# Wiring-Board-Nano_lay.net
KiCad netlist of a schematic drawn in EAGLE
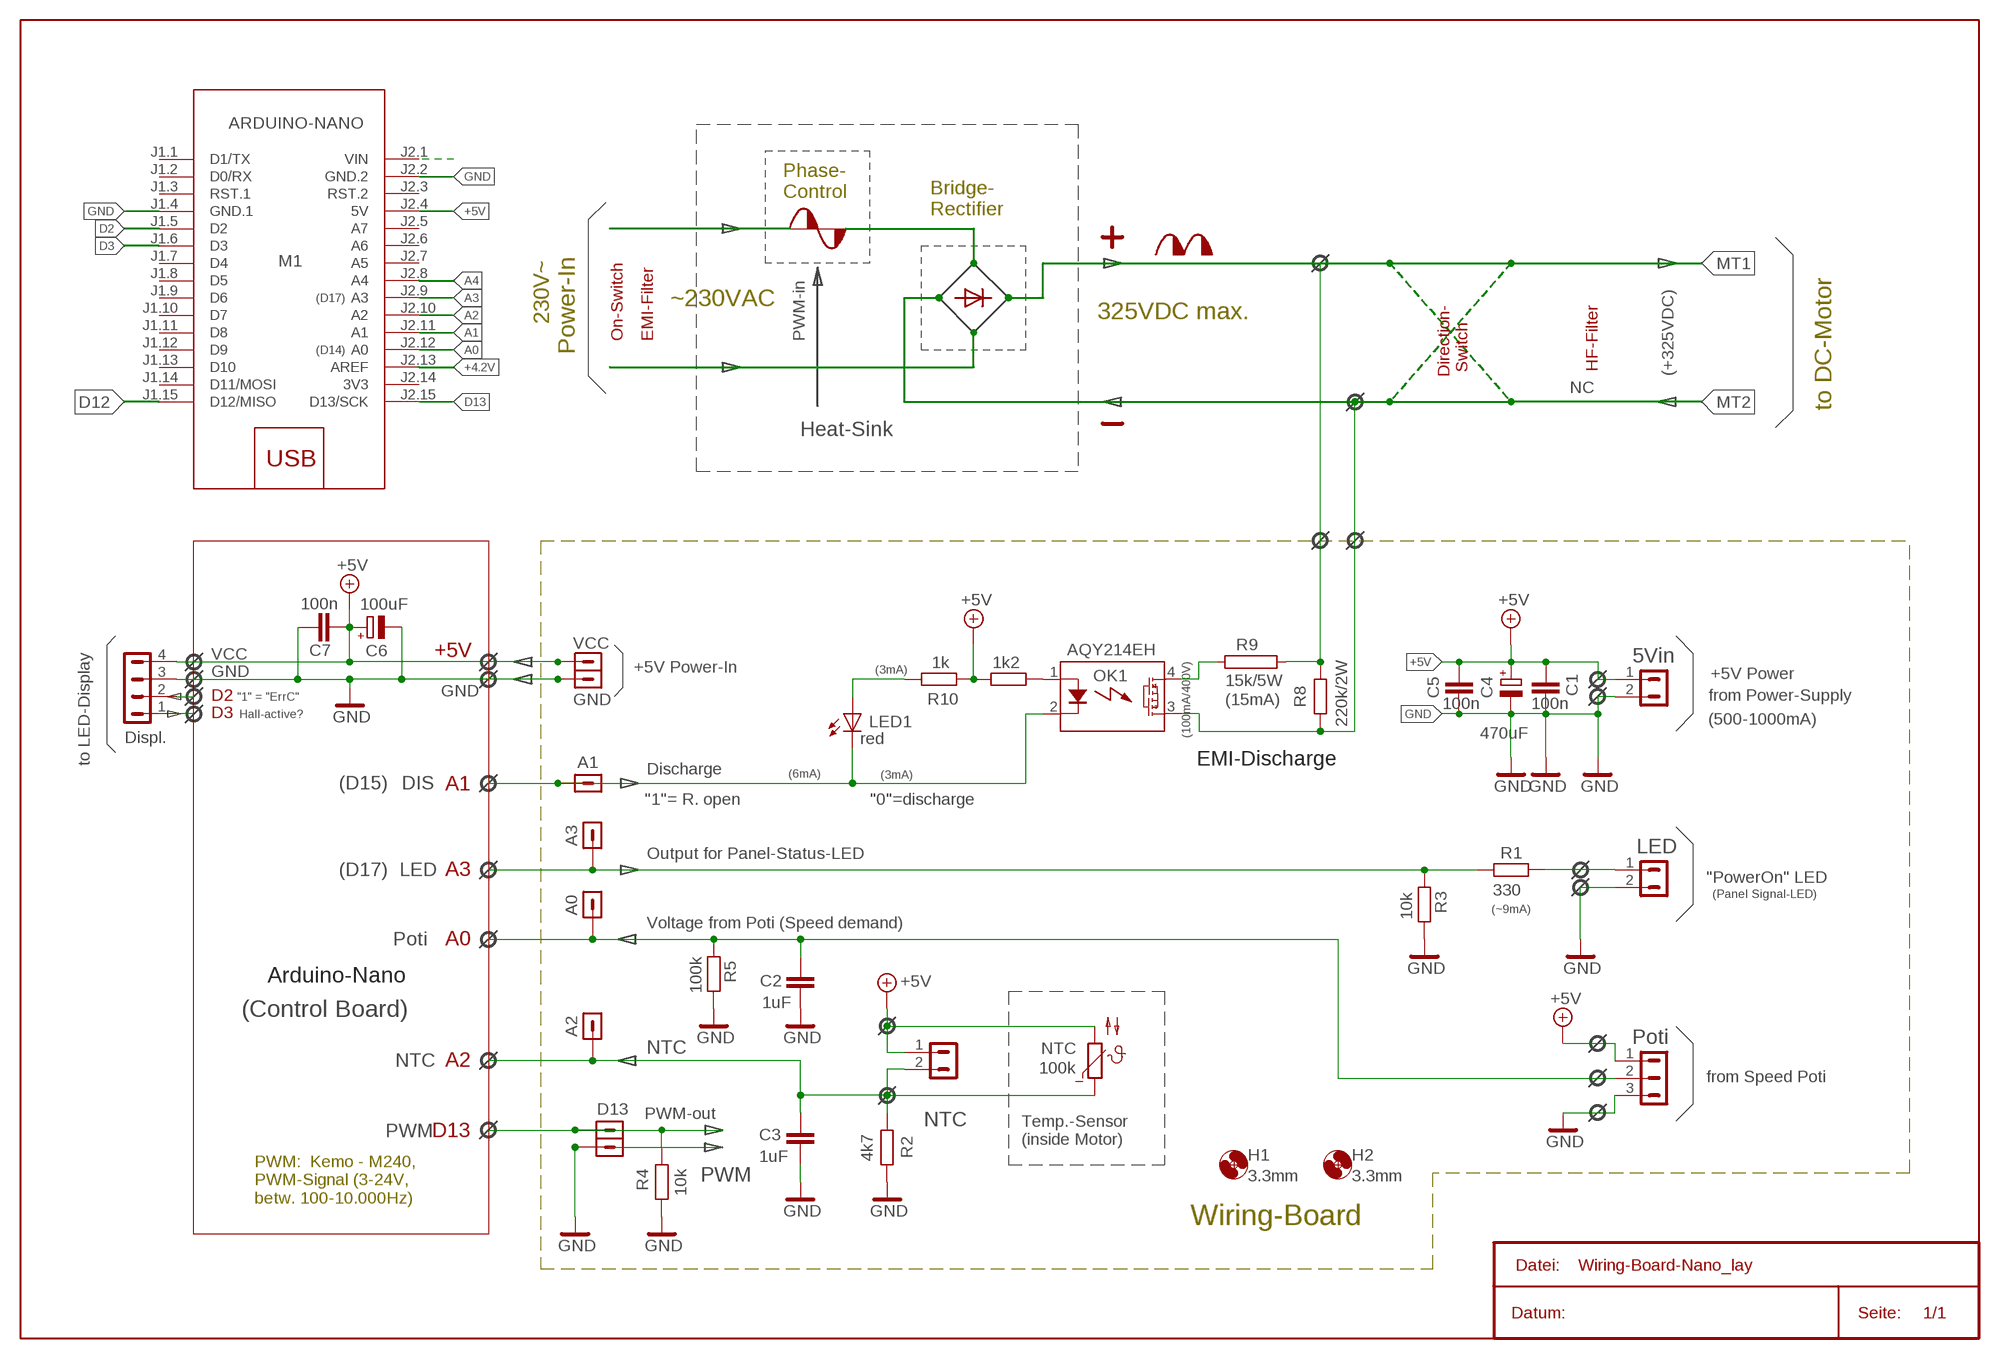
[diagram p0: schematic, sheet 1]

(export (version "E")
  (design (tool "Eeschema 10.0.6"))
  (components
    (comp (ref "C1")
      (value "100n")
      (footprint "eagle-import:C0805")
      (libsource (lib "eagle-import") (part "C-EUC0805"))
    )
    (comp (ref "C2")
      (value "1uF")
      (footprint "eagle-import:C0805")
      (libsource (lib "eagle-import") (part "C-EUC0805"))
    )
    (comp (ref "C3")
      (value "1uF")
      (footprint "eagle-import:C0805")
      (libsource (lib "eagle-import") (part "C-EUC0805"))
    )
    (comp (ref "C4")
      (value "470uF")
      (footprint "eagle-import:E3,5-8")
      (libsource (lib "eagle-import") (part "CPOL-EUE3.5-8"))
    )
    (comp (ref "C5")
      (value "100n")
      (footprint "eagle-import:C0805")
      (libsource (lib "eagle-import") (part "C-EUC0805"))
    )
    (comp (ref "C6")
      (value "100uF")
      (footprint "eagle-import:E2,5-7")
      (libsource (lib "eagle-import") (part "CPOL-EUE2.5-7"))
    )
    (comp (ref "C7")
      (value "100n")
      (footprint "eagle-import:C0805")
      (libsource (lib "eagle-import") (part "C-EUC0805"))
    )
    (comp (ref "H1")
      (value "3.3mm")
      (footprint "eagle-import:3,3")
      (libsource (lib "eagle-import") (part "MOUNT-HOLE3.3"))
    )
    (comp (ref "H2")
      (value "3.3mm")
      (footprint "eagle-import:3,3")
      (libsource (lib "eagle-import") (part "MOUNT-HOLE3.3"))
    )
    (comp (ref "LED1")
      (value "red")
      (footprint "eagle-import:CHIPLED_0805")
      (libsource (lib "eagle-import") (part "LEDCHIPLED_0805"))
    )
    (comp (ref "M1")
      (value "ARDUINO-NANO")
      (footprint "eagle-import:ARDUINO-NANO-3.0")
      (libsource (lib "eagle-import") (part "ARDUINO-NANO-3.0"))
    )
    (comp (ref "OK1")
      (value "AQY214EH")
      (footprint "eagle-import:GULLWING")
      (libsource (lib "eagle-import") (part "AQY"))
    )
    (comp (ref "R1")
      (value "330")
      (footprint "eagle-import:R0805")
      (libsource (lib "eagle-import") (part "R-EU_R0805"))
    )
    (comp (ref "R2")
      (value "4k7")
      (footprint "eagle-import:R0805")
      (libsource (lib "eagle-import") (part "R-EU_R0805"))
    )
    (comp (ref "R3")
      (value "10k")
      (footprint "eagle-import:R0805")
      (libsource (lib "eagle-import") (part "R-EU_R0805"))
    )
    (comp (ref "R4")
      (value "10k")
      (footprint "eagle-import:R0805")
      (libsource (lib "eagle-import") (part "R-EU_R0805"))
    )
    (comp (ref "R5")
      (value "100k")
      (footprint "eagle-import:R0805")
      (libsource (lib "eagle-import") (part "R-EU_R0805"))
    )
    (comp (ref "R8")
      (value "220k/2W")
      (footprint "eagle-import:0309_12")
      (libsource (lib "eagle-import") (part "R-EU_0309/12"))
    )
    (comp (ref "R9")
      (value "15k/5W")
      (footprint "eagle-import:KH206-8")
      (libsource (lib "eagle-import") (part "RKH206-8"))
    )
    (comp (ref "R10")
      (value "1k")
      (footprint "eagle-import:R0805")
      (libsource (lib "eagle-import") (part "R-EU_R0805"))
    )
    (comp (ref "R11")
      (value "1k2")
      (footprint "eagle-import:R0805")
      (libsource (lib "eagle-import") (part "R-EU_R0805"))
    )
    (comp (ref "SV1")
      (value "5Vin")
      (footprint "eagle-import:MA02-1")
      (libsource (lib "eagle-import") (part "MA02-10"))
    )
    (comp (ref "SV2")
      (value "LED")
      (footprint "eagle-import:MA02-1")
      (libsource (lib "eagle-import") (part "MA02-10"))
    )
    (comp (ref "SV3")
      (value "Poti")
      (footprint "eagle-import:MA03-1")
      (libsource (lib "eagle-import") (part "MA03-10"))
    )
    (comp (ref "SV4")
      (value "NTC")
      (footprint "eagle-import:MA02-1")
      (libsource (lib "eagle-import") (part "MA02-10"))
    )
    (comp (ref "SV6")
      (value "Displ.")
      (footprint "eagle-import:MA04-1")
      (libsource (lib "eagle-import") (part "MA04-10"))
    )
  )
  (nets
    (net (code "1") (name "+4.2V") (class "Default")
      (node (ref "M1") (pin "J2.13") (pinfunction "AREF_J2.13") (pintype "bidirectional"))
    )
    (net (code "2") (name "+5V") (class "Default")
      (node (ref "C1") (pin "1") (pinfunction "1_1") (pintype "passive"))
      (node (ref "C4") (pin "+") (pinfunction "+_+") (pintype "passive"))
      (node (ref "C5") (pin "1") (pinfunction "1_1") (pintype "passive"))
      (node (ref "C6") (pin "+") (pinfunction "+_+") (pintype "passive"))
      (node (ref "C7") (pin "1") (pinfunction "1_1") (pintype "passive"))
      (node (ref "M1") (pin "J2.4") (pinfunction "5V_J2.4") (pintype "power_in"))
      (node (ref "R10") (pin "2") (pinfunction "2_2") (pintype "passive"))
      (node (ref "R11") (pin "1") (pinfunction "1_1") (pintype "passive"))
      (node (ref "SV1") (pin "1") (pinfunction "1_1") (pintype "passive"))
      (node (ref "SV3") (pin "1") (pinfunction "1_1") (pintype "passive"))
      (node (ref "SV4") (pin "1") (pinfunction "1_1") (pintype "passive"))
      (node (ref "SV6") (pin "4") (pinfunction "4_4") (pintype "passive"))
    )
    (net (code "3") (name "/3V3") (class "Default")
      (node (ref "M1") (pin "J2.14") (pinfunction "3V3_J2.14") (pintype "power_in"))
    )
    (net (code "4") (name "A0") (class "Default")
      (node (ref "C2") (pin "1") (pinfunction "1_1") (pintype "passive"))
      (node (ref "M1") (pin "J2.12") (pinfunction "A0_J2.12") (pintype "bidirectional"))
      (node (ref "R5") (pin "1") (pinfunction "1_1") (pintype "passive"))
      (node (ref "SV3") (pin "2") (pinfunction "2_2") (pintype "passive"))
    )
    (net (code "5") (name "A1") (class "Default")
      (node (ref "LED1") (pin "C") (pinfunction "C_C") (pintype "passive"))
      (node (ref "M1") (pin "J2.11") (pinfunction "A1_J2.11") (pintype "bidirectional"))
      (node (ref "OK1") (pin "2") (pinfunction "K_2") (pintype "passive"))
    )
    (net (code "6") (name "A2") (class "Default")
      (node (ref "C3") (pin "1") (pinfunction "1_1") (pintype "passive"))
      (node (ref "M1") (pin "J2.10") (pinfunction "A2_J2.10") (pintype "bidirectional"))
      (node (ref "R2") (pin "2") (pinfunction "2_2") (pintype "passive"))
      (node (ref "SV4") (pin "2") (pinfunction "2_2") (pintype "passive"))
    )
    (net (code "7") (name "A3") (class "Default")
      (node (ref "M1") (pin "J2.9") (pinfunction "A3_J2.9") (pintype "bidirectional"))
      (node (ref "R1") (pin "1") (pinfunction "1_1") (pintype "passive"))
      (node (ref "R3") (pin "1") (pinfunction "1_1") (pintype "passive"))
    )
    (net (code "8") (name "A4") (class "Default")
      (node (ref "M1") (pin "J2.8") (pinfunction "A4_J2.8") (pintype "bidirectional"))
    )
    (net (code "9") (name "D2") (class "Default")
      (node (ref "M1") (pin "J1.5") (pinfunction "D2_J1.5") (pintype "bidirectional"))
      (node (ref "SV6") (pin "2") (pinfunction "2_2") (pintype "passive"))
    )
    (net (code "10") (name "D3") (class "Default")
      (node (ref "M1") (pin "J1.6") (pinfunction "D3_J1.6") (pintype "bidirectional"))
      (node (ref "SV6") (pin "1") (pinfunction "1_1") (pintype "passive"))
    )
    (net (code "11") (name "D12") (class "Default")
      (node (ref "M1") (pin "J1.15") (pinfunction "D12/MISO_J1.15") (pintype "bidirectional"))
    )
    (net (code "12") (name "D13") (class "Default")
      (node (ref "M1") (pin "J2.15") (pinfunction "D13/SCK_J2.15") (pintype "bidirectional"))
      (node (ref "R4") (pin "1") (pinfunction "1_1") (pintype "passive"))
    )
    (net (code "13") (name "GND") (class "Default")
      (node (ref "C1") (pin "2") (pinfunction "2_2") (pintype "passive"))
      (node (ref "C2") (pin "2") (pinfunction "2_2") (pintype "passive"))
      (node (ref "C3") (pin "2") (pinfunction "2_2") (pintype "passive"))
      (node (ref "C4") (pin "-") (pinfunction "-_-") (pintype "passive"))
      (node (ref "C5") (pin "2") (pinfunction "2_2") (pintype "passive"))
      (node (ref "C6") (pin "-") (pinfunction "-_-") (pintype "passive"))
      (node (ref "C7") (pin "2") (pinfunction "2_2") (pintype "passive"))
      (node (ref "M1") (pin "J1.4") (pinfunction "GND.1_J1.4") (pintype "power_in"))
      (node (ref "M1") (pin "J2.2") (pinfunction "GND.2_J2.2") (pintype "power_in"))
      (node (ref "R2") (pin "1") (pinfunction "1_1") (pintype "passive"))
      (node (ref "R3") (pin "2") (pinfunction "2_2") (pintype "passive"))
      (node (ref "R4") (pin "2") (pinfunction "2_2") (pintype "passive"))
      (node (ref "R5") (pin "2") (pinfunction "2_2") (pintype "passive"))
      (node (ref "SV1") (pin "2") (pinfunction "2_2") (pintype "passive"))
      (node (ref "SV2") (pin "2") (pinfunction "2_2") (pintype "passive"))
      (node (ref "SV3") (pin "3") (pinfunction "3_3") (pintype "passive"))
      (node (ref "SV6") (pin "3") (pinfunction "3_3") (pintype "passive"))
    )
    (net (code "14") (name "MT1") (class "Default")
      (node (ref "R8") (pin "2") (pinfunction "2_2") (pintype "passive"))
      (node (ref "R9") (pin "2") (pinfunction "2_2") (pintype "passive"))
    )
    (net (code "16") (name "Net-(LED1-PadA)") (class "Default")
      (node (ref "LED1") (pin "A") (pinfunction "A_A") (pintype "passive"))
      (node (ref "R10") (pin "1") (pinfunction "1_1") (pintype "passive"))
    )
    (net (code "17") (name "Net-(OK1-A)") (class "Default")
      (node (ref "OK1") (pin "1") (pinfunction "A_1") (pintype "passive"))
      (node (ref "R11") (pin "2") (pinfunction "2_2") (pintype "passive"))
    )
    (net (code "18") (name "Net-(OK1-DS1)") (class "Default")
      (node (ref "OK1") (pin "4") (pinfunction "DS1_4") (pintype "passive"))
      (node (ref "R9") (pin "1") (pinfunction "1_1") (pintype "passive"))
    )
    (net (code "19") (name "Net-(OK1-DS2)") (class "Default")
      (node (ref "OK1") (pin "3") (pinfunction "DS2_3") (pintype "passive"))
      (node (ref "R8") (pin "1") (pinfunction "1_1") (pintype "passive"))
    )
    (net (code "20") (name "Net-(R1-Pad2)") (class "Default")
      (node (ref "R1") (pin "2") (pinfunction "2_2") (pintype "passive"))
      (node (ref "SV2") (pin "1") (pinfunction "1_1") (pintype "passive"))
    )
    (net (code "21") (name "unconnected-(M1-A5-PadJ2.7)") (class "Default")
      (node (ref "M1") (pin "J2.7") (pinfunction "A5_J2.7") (pintype "bidirectional"))
    )
    (net (code "22") (name "unconnected-(M1-A6-PadJ2.6)") (class "Default")
      (node (ref "M1") (pin "J2.6") (pinfunction "A6_J2.6") (pintype "bidirectional"))
    )
    (net (code "23") (name "unconnected-(M1-A7-PadJ2.5)") (class "Default")
      (node (ref "M1") (pin "J2.5") (pinfunction "A7_J2.5") (pintype "bidirectional"))
    )
    (net (code "24") (name "unconnected-(M1-D0{slash}RX-PadJ1.2)") (class "Default")
      (node (ref "M1") (pin "J1.2") (pinfunction "D0/RX_J1.2") (pintype "bidirectional"))
    )
    (net (code "25") (name "unconnected-(M1-D1{slash}TX-PadJ1.1)") (class "Default")
      (node (ref "M1") (pin "J1.1") (pinfunction "D1/TX_J1.1") (pintype "bidirectional"))
    )
    (net (code "26") (name "unconnected-(M1-D4-PadJ1.7)") (class "Default")
      (node (ref "M1") (pin "J1.7") (pinfunction "D4_J1.7") (pintype "bidirectional"))
    )
    (net (code "27") (name "unconnected-(M1-D5-PadJ1.8)") (class "Default")
      (node (ref "M1") (pin "J1.8") (pinfunction "D5_J1.8") (pintype "bidirectional"))
    )
    (net (code "28") (name "unconnected-(M1-D6-PadJ1.9)") (class "Default")
      (node (ref "M1") (pin "J1.9") (pinfunction "D6_J1.9") (pintype "bidirectional"))
    )
    (net (code "29") (name "unconnected-(M1-D7-PadJ1.10)") (class "Default")
      (node (ref "M1") (pin "J1.10") (pinfunction "D7_J1.10") (pintype "bidirectional"))
    )
    (net (code "30") (name "unconnected-(M1-D8-PadJ1.11)") (class "Default")
      (node (ref "M1") (pin "J1.11") (pinfunction "D8_J1.11") (pintype "bidirectional"))
    )
    (net (code "31") (name "unconnected-(M1-D9-PadJ1.12)") (class "Default")
      (node (ref "M1") (pin "J1.12") (pinfunction "D9_J1.12") (pintype "bidirectional"))
    )
    (net (code "32") (name "unconnected-(M1-D10-PadJ1.13)") (class "Default")
      (node (ref "M1") (pin "J1.13") (pinfunction "D10_J1.13") (pintype "bidirectional"))
    )
    (net (code "33") (name "unconnected-(M1-D11{slash}MOSI-PadJ1.14)") (class "Default")
      (node (ref "M1") (pin "J1.14") (pinfunction "D11/MOSI_J1.14") (pintype "bidirectional"))
    )
    (net (code "34") (name "unconnected-(M1-RST.1-PadJ1.3)") (class "Default")
      (node (ref "M1") (pin "J1.3") (pinfunction "RST.1_J1.3") (pintype "bidirectional"))
    )
    (net (code "35") (name "unconnected-(M1-RST.2-PadJ2.3)") (class "Default")
      (node (ref "M1") (pin "J2.3") (pinfunction "RST.2_J2.3") (pintype "bidirectional"))
    )
    (net (code "36") (name "unconnected-(M1-VIN-PadJ2.1)") (class "Default")
      (node (ref "M1") (pin "J2.1") (pinfunction "VIN_J2.1") (pintype "power_in"))
    )
  )
)
